# MCU.net
KiCad netlist of a schematic drawn in Altium Designer
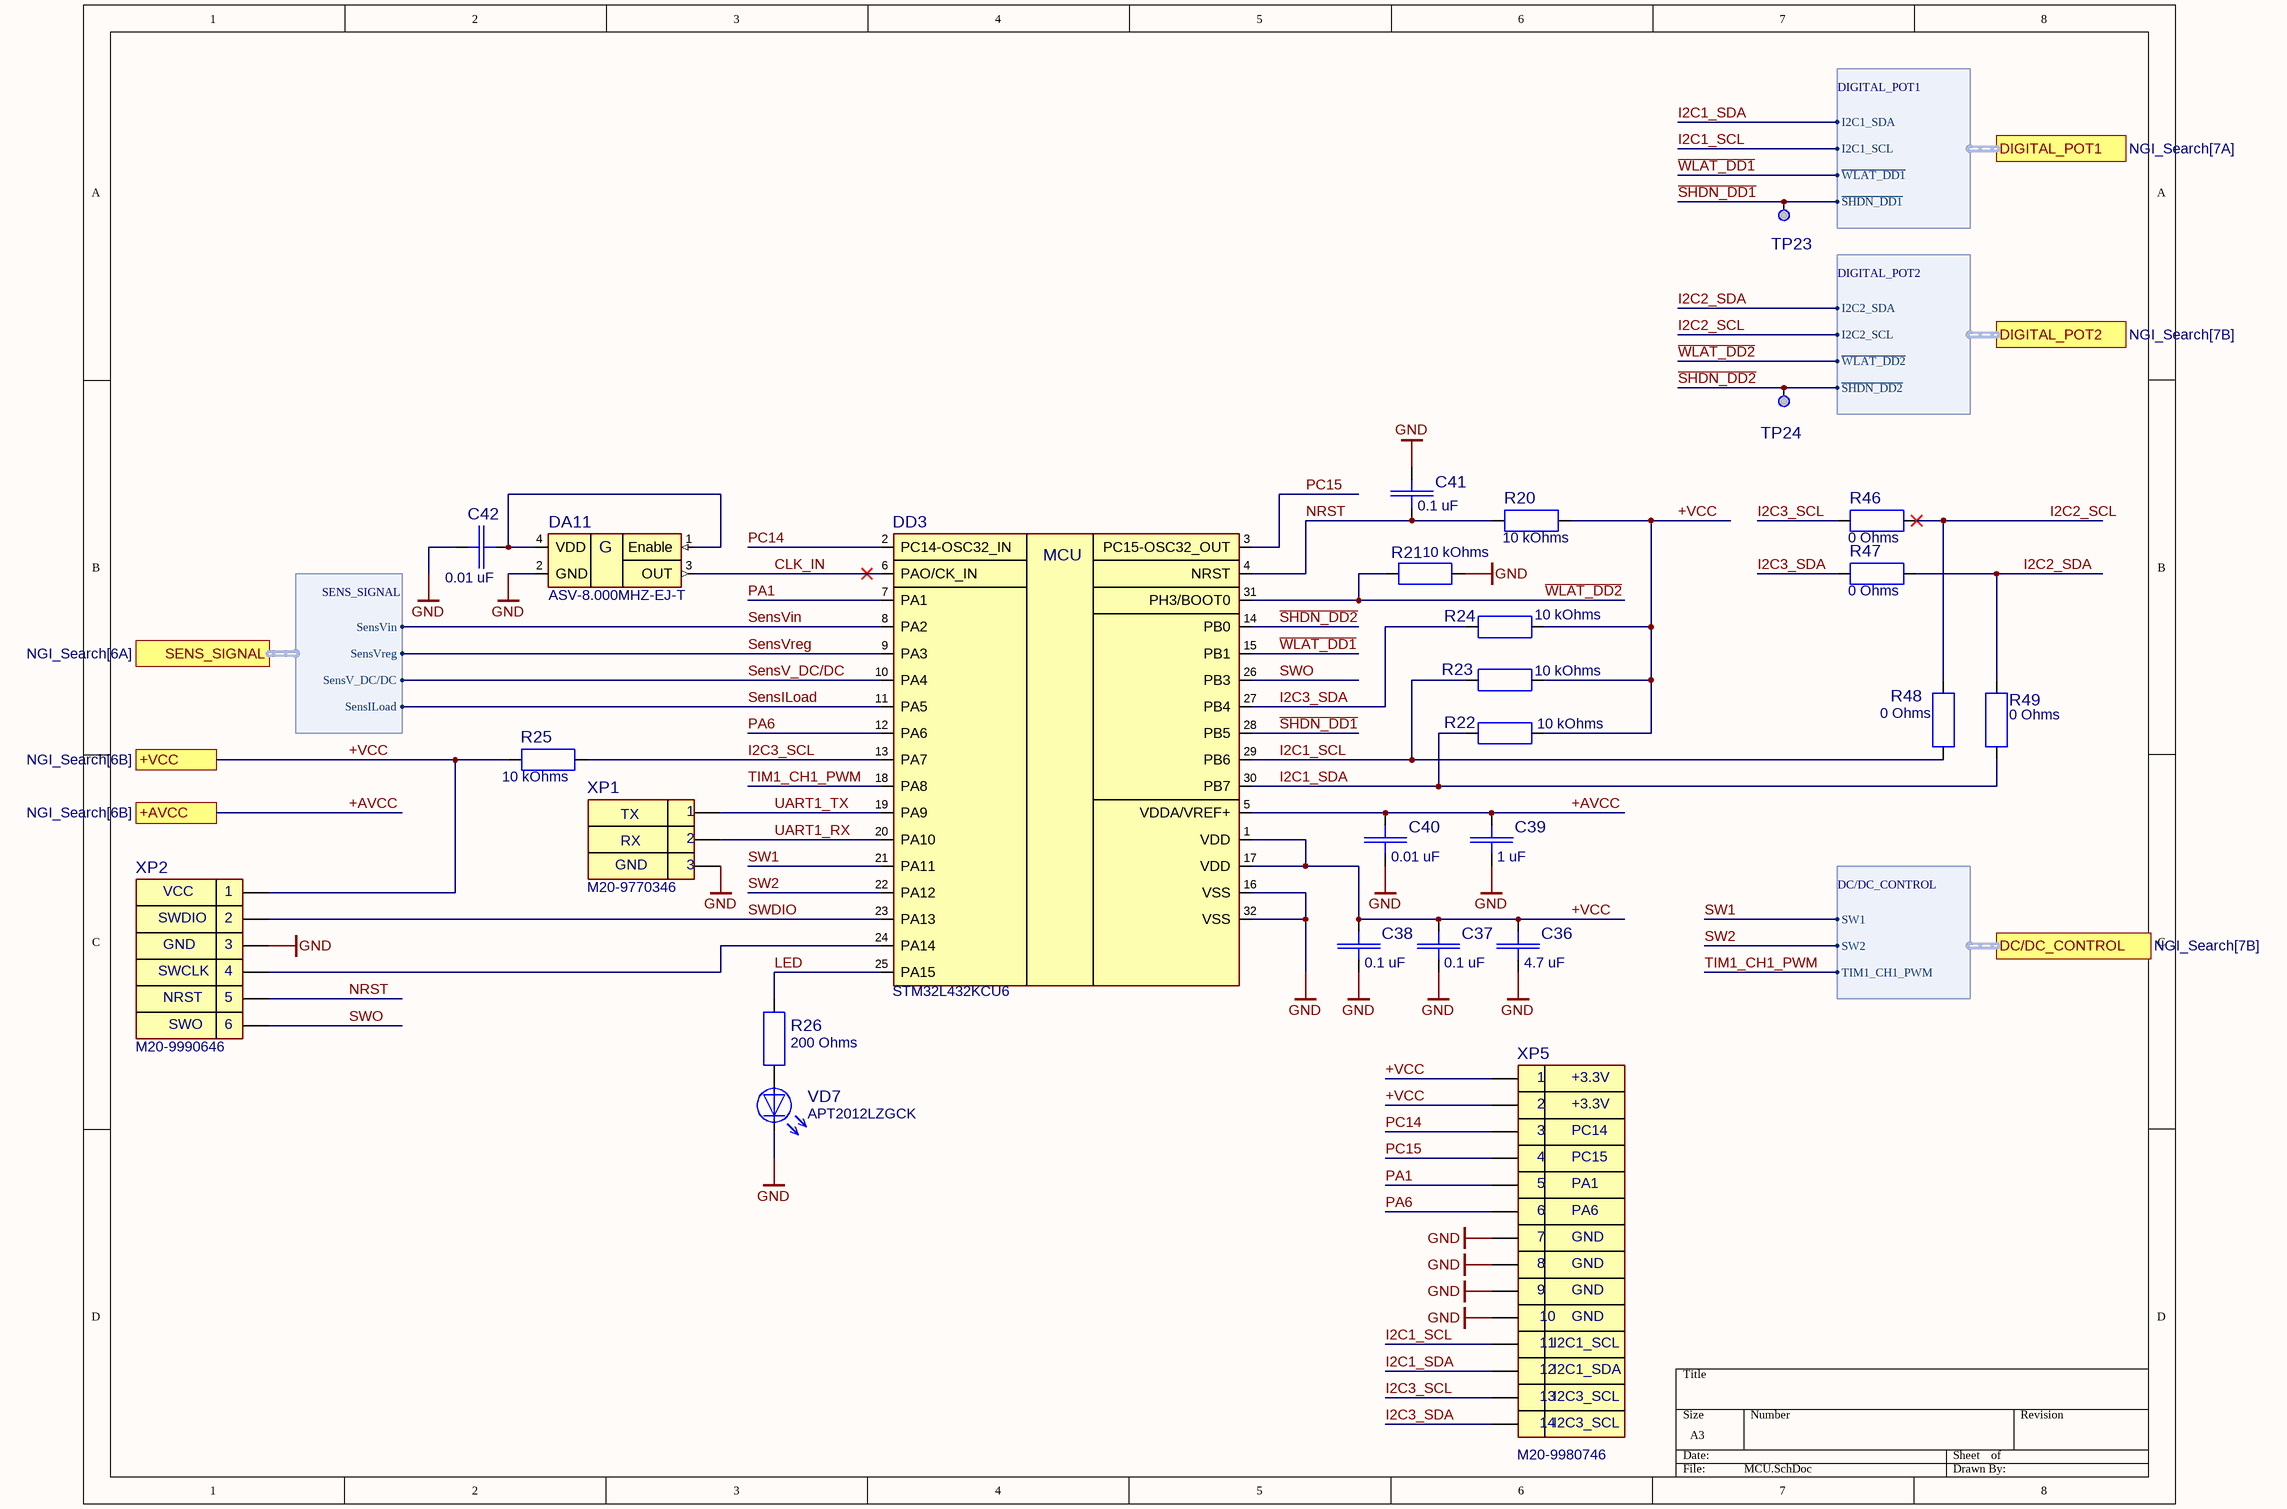
[diagram p0: MCU.SchDoc]

(export (version "E")
  (design (tool "Eeschema 10.0.6"))
  (components
    (comp (ref "C36")
      (value "4.7 uF")
      (footprint "Capacitor0805_THICKNESS1.25")
      (description "Multilayer Ceramic Capacitors MLCC - SMD/SMT 4.7uF+/-10% 25V X5R 0805")
      (fields
        (field (name "MANUFACTURER") "Samsung Electro-Mechanics")
        (field (name "MANUFACTURERPARTNUMBER") "CL21A475KAQNNNF")
      )
      (libsource (lib "NGI_Search") (part "CL21A475KAQNNNF"))
    )
    (comp (ref "C37")
      (value "0.1 uF")
      (footprint "Capacitor0805_THICKNESS0.8")
      (description "Multilayer Ceramic Capacitors MLCC - SMD/SMT 100nF+/-10% 50V X7R 0805")
      (fields (field (name "TOLERANCE") "10%") (field (name "MANUFACTURERPARTNUMBER") "CL21B104KBCNNWC"))
      (libsource (lib "NGI_Search") (part "CL21B104KBCNNWC"))
    )
    (comp (ref "C38")
      (value "0.1 uF")
      (footprint "Capacitor0805_THICKNESS0.8")
      (description "Multilayer Ceramic Capacitors MLCC - SMD/SMT 100nF+/-10% 50V X7R 0805")
      (fields (field (name "TOLERANCE") "10%") (field (name "MANUFACTURERPARTNUMBER") "CL21B104KBCNNWC"))
      (libsource (lib "NGI_Search") (part "CL21B104KBCNNWC"))
    )
    (comp (ref "C39")
      (value "1 uF")
      (footprint "Capacitor0805_THICKNESS1.25")
      (description "Multilayer Ceramic Capacitors MLCC - SMD/SMT 1uF+/-10% 25V X7R 20 0805")
      (fields
        (field (name "MANUFACTURER") "Samsung Electro-Mechanics")
        (field (name "MANUFACTURERPARTNUMBER") "CL21B105KAFNFNE")
      )
      (libsource (lib "NGI_Search") (part "CL21B105KAFNFNE"))
    )
    (comp (ref "C40")
      (value "0.01 uF")
      (footprint "Capacitor0805_THICKNESS0.8")
      (description "Multilayer Ceramic Capacitors MLCC - SMD/SMT 10nF+/-10% 50V X7R 2 0805")
      (fields
        (field (name "MANUFACTURER") "Samsung Electro-Mechanics")
        (field (name "MANUFACTURERPARTNUMBER") "CL21B103KBANNNL")
      )
      (libsource (lib "NGI_Search") (part "CL21B103KBANNNL"))
    )
    (comp (ref "C41")
      (value "0.1 uF")
      (footprint "Capacitor0805_THICKNESS0.8")
      (description "Multilayer Ceramic Capacitors MLCC - SMD/SMT 100nF+/-10% 50V X7R 0805")
      (fields (field (name "TOLERANCE") "10%") (field (name "MANUFACTURERPARTNUMBER") "CL21B104KBCNNWC"))
      (libsource (lib "NGI_Search") (part "CL21B104KBCNNWC"))
    )
    (comp (ref "C42")
      (value "0.01 uF")
      (footprint "Capacitor0805_THICKNESS0.8")
      (description "Multilayer Ceramic Capacitors MLCC - SMD/SMT 10nF+/-10% 50V X7R 2 0805")
      (fields
        (field (name "MANUFACTURER") "Samsung Electro-Mechanics")
        (field (name "MANUFACTURERPARTNUMBER") "CL21B103KBANNNL")
      )
      (libsource (lib "NGI_Search") (part "CL21B103KBANNNL"))
    )
    (comp (ref "DA11")
      (value "ASV-8.000MHZ-EJ-T")
      (footprint "HCMOS 7 mm x 5 mm")
      (description "Standard Clock Oscillators XTAL OSC XO 8.0000MHZ HCMOS SMD")
      (fields (field (name "MANUFACTURER") "ABRACON") (field (name "MOUSER PART NUMBER") "815-ASV-8-EJ-T"))
      (libsource (lib "NGI_Search") (part "ASV-8.000MHZ-EJ-T"))
    )
    (comp (ref "DD3")
      (value "STM32L432KCU6")
      (footprint "UFQFPN-32")
      (description "ARM Microcontrollers - MCU Ultra-low-power FPU Arm Cortex-M4 MCU 80 MHz 256 Kbytes of Flash , USB")
      (fields
        (field (name "MANUFACTURER") "STMicroelectronics")
        (field (name "MOUSER PART NUMBER") "511-STM32L432KCU6")
      )
      (libsource (lib "NGI_Search") (part "STM32L432KCU6"))
    )
    (comp (ref "R20")
      (value "10 kOhms")
      (footprint "Resistor0805_THICKNESS0.6")
      (description "Thick Film Resistors 10 kOhms 125 mW 0805 1%")
      (fields (field (name "MANUFACTURER") "YAGEO") (field (name "MANUFACTURERPARTNUMBER") "RC0805FR-0710KL"))
      (libsource (lib "NGI_Search") (part "RC0805FR-0710KL"))
    )
    (comp (ref "R21")
      (value "10 kOhms")
      (footprint "Resistor0805_THICKNESS0.6")
      (description "Thick Film Resistors 10 kOhms 125 mW 0805 1%")
      (fields (field (name "MANUFACTURER") "YAGEO") (field (name "MANUFACTURERPARTNUMBER") "RC0805FR-0710KL"))
      (libsource (lib "NGI_Search") (part "RC0805FR-0710KL"))
    )
    (comp (ref "R22")
      (value "10 kOhms")
      (footprint "Resistor0805_THICKNESS0.6")
      (description "Thick Film Resistors 10 kOhms 125 mW 0805 1%")
      (fields (field (name "MANUFACTURER") "YAGEO") (field (name "MANUFACTURERPARTNUMBER") "RC0805FR-0710KL"))
      (libsource (lib "NGI_Search") (part "RC0805FR-0710KL"))
    )
    (comp (ref "R23")
      (value "10 kOhms")
      (footprint "Resistor0805_THICKNESS0.6")
      (description "Thick Film Resistors 10 kOhms 125 mW 0805 1%")
      (fields (field (name "MANUFACTURER") "YAGEO") (field (name "MANUFACTURERPARTNUMBER") "RC0805FR-0710KL"))
      (libsource (lib "NGI_Search") (part "RC0805FR-0710KL"))
    )
    (comp (ref "R24")
      (value "10 kOhms")
      (footprint "Resistor0805_THICKNESS0.6")
      (description "Thick Film Resistors 10 kOhms 125 mW 0805 1%")
      (fields (field (name "MANUFACTURER") "YAGEO") (field (name "MANUFACTURERPARTNUMBER") "RC0805FR-0710KL"))
      (libsource (lib "NGI_Search") (part "RC0805FR-0710KL"))
    )
    (comp (ref "R25")
      (value "10 kOhms")
      (footprint "Resistor0805_THICKNESS0.6")
      (description "Thick Film Resistors 10 kOhms 125 mW 0805 1%")
      (fields (field (name "MANUFACTURER") "YAGEO") (field (name "MANUFACTURERPARTNUMBER") "RC0805FR-0710KL"))
      (libsource (lib "NGI_Search") (part "RC0805FR-0710KL"))
    )
    (comp (ref "R26")
      (value "200 Ohms")
      (footprint "Resistor0805_THICKNESS0.6")
      (description "Thick Film Resistors 200Ohms 1/8W 0805 1%")
      (fields
        (field (name "MANUFACTURER") "YAGEO")
        (field (name "MANUFACTURERPARTNUMBER") "RC0805FR-10200RL")
      )
      (libsource (lib "NGI_Search") (part "RC0805FR-10200RL"))
    )
    (comp (ref "R46")
      (value "0 Ohms")
      (footprint "Resistor0805_THICKNESS0.6")
      (description "Thick Film Resistors 0 Ohms 125 mW 0805 1%")
      (fields (field (name "MANUFACTURER") "YAGEO") (field (name "MANUFACTURERPARTNUMBER") "RC0805FR-070RL"))
      (libsource (lib "NGI_Search") (part "RC0805FR-070RL"))
    )
    (comp (ref "R47")
      (value "0 Ohms")
      (footprint "Resistor0805_THICKNESS0.6")
      (description "Thick Film Resistors 0 Ohms 125 mW 0805 1%")
      (fields (field (name "MANUFACTURER") "YAGEO") (field (name "MANUFACTURERPARTNUMBER") "RC0805FR-070RL"))
      (libsource (lib "NGI_Search") (part "RC0805FR-070RL"))
    )
    (comp (ref "R48")
      (value "0 Ohms")
      (footprint "Resistor0805_THICKNESS0.6")
      (description "Thick Film Resistors 0 Ohms 125 mW 0805 1%")
      (fields (field (name "MANUFACTURER") "YAGEO") (field (name "MANUFACTURERPARTNUMBER") "RC0805FR-070RL"))
      (libsource (lib "NGI_Search") (part "RC0805FR-070RL"))
    )
    (comp (ref "R49")
      (value "0 Ohms")
      (footprint "Resistor0805_THICKNESS0.6")
      (description "Thick Film Resistors 0 Ohms 125 mW 0805 1%")
      (fields (field (name "MANUFACTURER") "YAGEO") (field (name "MANUFACTURERPARTNUMBER") "RC0805FR-070RL"))
      (libsource (lib "NGI_Search") (part "RC0805FR-070RL"))
    )
    (comp (ref "TP23")
      (value "test point")
      (footprint "test point")
      (libsource (lib "NGI_Search") (part "test point"))
    )
    (comp (ref "TP24")
      (value "test point")
      (footprint "test point")
      (libsource (lib "NGI_Search") (part "test point"))
    )
    (comp (ref "VD7")
      (value "APT2012LZGCK")
      (footprint "APT2012LZGCK0805_LEDs")
      (description "Standard LEDs - SMD 2.0X1.2MM LOW CRNT")
      (fields
        (field (name "MANUFACTURER") "Kingbright")
        (field (name "MOUSER PART NUMBER") "604-APT2012LZGCK")
      )
      (libsource (lib "NGI_Search") (part "APT2012LZGCK"))
    )
    (comp (ref "XP1")
      (value "M20-9770346")
      (footprint "3 VERTICAL PIN Pitch: 2.54 mm")
      (description "Headers & Wire Housings 03 SIL VERTICAL PIN HEADER TIN")
      (fields (field (name "MANUFACTURER") "Harwin") (field (name "MOUSER PART NUMBER") "855-M20-9770346"))
      (libsource (lib "NGI_Search") (part "M20-9770346"))
    )
    (comp (ref "XP2")
      (value "M20-9990646")
      (footprint "6 VERTICAL PIN Pitch: 2.54 mm")
      (description "Headers & Wire Housings 06 SIL VERTICAL PIN HEADER TIN")
      (fields (field (name "MANUFACTURER") "Harwin"))
      (libsource (lib "NGI_Search") (part "M20-9990646"))
    )
    (comp (ref "XP5")
      (value "M20-9980746")
      (footprint "M20-9980746")
      (description "Headers & Wire Housings 07+07 DIL VERTICAL PIN HEADER TIN")
      (fields (field (name "MANUFACTURER") "Harwin") (field (name "MOUSER PART NUMBER") "855-M20-9980746"))
      (libsource (lib "NGI_Search") (part "M20-9980746"))
    )
  )
  (nets
    (net (code "5") (name "/+AVCC") (class "Default")
      (node (ref "C39") (pin "2") (pinfunction "2_2") (pintype "passive"))
      (node (ref "C40") (pin "2") (pinfunction "2_2") (pintype "passive"))
      (node (ref "DD3") (pin "5") (pinfunction "VDDA/VREF+_5") (pintype "power_in"))
    )
    (net (code "6") (name "/+VCC") (class "Default")
      (node (ref "C36") (pin "2") (pinfunction "2_2") (pintype "passive"))
      (node (ref "C37") (pin "2") (pinfunction "2_2") (pintype "passive"))
      (node (ref "C38") (pin "2") (pinfunction "2_2") (pintype "passive"))
      (node (ref "DD3") (pin "1") (pinfunction "VDD_1") (pintype "power_in"))
      (node (ref "DD3") (pin "17") (pinfunction "VDD_17") (pintype "power_in"))
      (node (ref "R20") (pin "2") (pinfunction "2_2") (pintype "passive"))
      (node (ref "R22") (pin "1") (pinfunction "1_1") (pintype "passive"))
      (node (ref "R23") (pin "2") (pinfunction "2_2") (pintype "passive"))
      (node (ref "R24") (pin "1") (pinfunction "1_1") (pintype "passive"))
      (node (ref "R25") (pin "1") (pinfunction "1_1") (pintype "passive"))
      (node (ref "XP2") (pin "1") (pintype "passive"))
      (node (ref "XP5") (pin "1") (pintype "passive"))
      (node (ref "XP5") (pin "2") (pintype "passive"))
    )
    (net (code "7") (name "/CLK_IN") (class "Default")
      (node (ref "DA11") (pin "3") (pinfunction "OUT_3") (pintype "output"))
      (node (ref "DD3") (pin "6") (pinfunction "PAO/CK_IN_6") (pintype "bidirectional"))
    )
    (net (code "8") (name "/I2C1_SCL") (class "Default")
      (node (ref "DD3") (pin "29") (pinfunction "PB6_29") (pintype "bidirectional"))
      (node (ref "R23") (pin "1") (pinfunction "1_1") (pintype "passive"))
      (node (ref "R48") (pin "1") (pinfunction "1_1") (pintype "passive"))
      (node (ref "XP5") (pin "11") (pinfunction "11_11") (pintype "passive"))
    )
    (net (code "9") (name "/I2C1_SDA") (class "Default")
      (node (ref "DD3") (pin "30") (pinfunction "PB7_30") (pintype "bidirectional"))
      (node (ref "R22") (pin "2") (pinfunction "2_2") (pintype "passive"))
      (node (ref "R49") (pin "1") (pinfunction "1_1") (pintype "passive"))
      (node (ref "XP5") (pin "12") (pinfunction "12_12") (pintype "passive"))
    )
    (net (code "10") (name "/I2C2_SCL") (class "Default")
      (node (ref "R46") (pin "2") (pinfunction "2_2") (pintype "passive"))
      (node (ref "R48") (pin "2") (pinfunction "2_2") (pintype "passive"))
    )
    (net (code "11") (name "/I2C2_SDA") (class "Default")
      (node (ref "R47") (pin "2") (pinfunction "2_2") (pintype "passive"))
      (node (ref "R49") (pin "2") (pinfunction "2_2") (pintype "passive"))
    )
    (net (code "12") (name "/I2C3_SCL") (class "Default")
      (node (ref "DD3") (pin "13") (pinfunction "PA7_13") (pintype "bidirectional"))
      (node (ref "R25") (pin "2") (pinfunction "2_2") (pintype "passive"))
      (node (ref "R46") (pin "1") (pinfunction "1_1") (pintype "passive"))
      (node (ref "XP5") (pin "13") (pinfunction "13_13") (pintype "passive"))
    )
    (net (code "13") (name "/I2C3_SDA") (class "Default")
      (node (ref "DD3") (pin "27") (pinfunction "PB4_27") (pintype "bidirectional"))
      (node (ref "R24") (pin "2") (pinfunction "2_2") (pintype "passive"))
      (node (ref "R47") (pin "1") (pinfunction "1_1") (pintype "passive"))
      (node (ref "XP5") (pin "14") (pinfunction "14_14") (pintype "passive"))
    )
    (net (code "14") (name "/LED") (class "Default")
      (node (ref "DD3") (pin "25") (pinfunction "PA15_25") (pintype "bidirectional"))
      (node (ref "R26") (pin "2") (pinfunction "2_2") (pintype "passive"))
    )
    (net (code "15") (name "/NRST") (class "Default")
      (node (ref "C41") (pin "2") (pinfunction "2_2") (pintype "passive"))
      (node (ref "DD3") (pin "4") (pinfunction "NRST_4") (pintype "bidirectional"))
      (node (ref "R20") (pin "1") (pinfunction "1_1") (pintype "passive"))
      (node (ref "XP2") (pin "5") (pintype "passive"))
    )
    (net (code "16") (name "/PA1") (class "Default")
      (node (ref "DD3") (pin "7") (pinfunction "PA1_7") (pintype "bidirectional"))
      (node (ref "XP5") (pin "5") (pintype "passive"))
    )
    (net (code "17") (name "/PA6") (class "Default")
      (node (ref "DD3") (pin "12") (pinfunction "PA6_12") (pintype "bidirectional"))
      (node (ref "XP5") (pin "6") (pintype "passive"))
    )
    (net (code "18") (name "/PC14") (class "Default")
      (node (ref "DD3") (pin "2") (pinfunction "PC14-OSC32_IN_2") (pintype "bidirectional"))
      (node (ref "XP5") (pin "3") (pintype "passive"))
    )
    (net (code "19") (name "/PC15") (class "Default")
      (node (ref "DD3") (pin "3") (pinfunction "PC15-OSC32_OUT_3") (pintype "bidirectional"))
      (node (ref "XP5") (pin "4") (pintype "passive"))
    )
    (net (code "20") (name "/SW1") (class "Default")
      (node (ref "DD3") (pin "21") (pinfunction "PA11_21") (pintype "bidirectional"))
    )
    (net (code "21") (name "/SW2") (class "Default")
      (node (ref "DD3") (pin "22") (pinfunction "PA12_22") (pintype "bidirectional"))
    )
    (net (code "22") (name "/SWDIO") (class "Default")
      (node (ref "DD3") (pin "23") (pinfunction "PA13_23") (pintype "bidirectional"))
      (node (ref "XP2") (pin "2") (pintype "passive"))
    )
    (net (code "23") (name "/SWO") (class "Default")
      (node (ref "DD3") (pin "26") (pinfunction "PB3_26") (pintype "bidirectional"))
      (node (ref "XP2") (pin "6") (pintype "passive"))
    )
    (net (code "24") (name "/SensILoad") (class "Default")
      (node (ref "DD3") (pin "11") (pinfunction "PA5_11") (pintype "bidirectional"))
    )
    (net (code "25") (name "/SensV_DC{slash}DC") (class "Default")
      (node (ref "DD3") (pin "10") (pinfunction "PA4_10") (pintype "bidirectional"))
    )
    (net (code "26") (name "/SensVin") (class "Default")
      (node (ref "DD3") (pin "8") (pinfunction "PA2_8") (pintype "bidirectional"))
    )
    (net (code "27") (name "/SensVreg") (class "Default")
      (node (ref "DD3") (pin "9") (pinfunction "PA3_9") (pintype "bidirectional"))
    )
    (net (code "28") (name "/TIM1_CH1_PWM") (class "Default")
      (node (ref "DD3") (pin "18") (pinfunction "PA8_18") (pintype "bidirectional"))
    )
    (net (code "29") (name "/UART1_RX") (class "Default")
      (node (ref "DD3") (pin "20") (pinfunction "PA10_20") (pintype "bidirectional"))
      (node (ref "XP1") (pin "2") (pintype "passive"))
    )
    (net (code "30") (name "/UART1_TX") (class "Default")
      (node (ref "DD3") (pin "19") (pinfunction "PA9_19") (pintype "bidirectional"))
      (node (ref "XP1") (pin "1") (pintype "passive"))
    )
    (net (code "35") (name "/~{SHDN_DD1}") (class "Default")
      (node (ref "DD3") (pin "28") (pinfunction "PB5_28") (pintype "bidirectional"))
      (node (ref "TP23") (pin "1") (pinfunction "1_1") (pintype "passive"))
    )
    (net (code "36") (name "/~{SHDN_DD2}") (class "Default")
      (node (ref "DD3") (pin "14") (pinfunction "PB0_14") (pintype "bidirectional"))
      (node (ref "TP24") (pin "1") (pinfunction "1_1") (pintype "passive"))
    )
    (net (code "37") (name "/~{WLAT_DD1}") (class "Default")
      (node (ref "DD3") (pin "15") (pinfunction "PB1_15") (pintype "bidirectional"))
    )
    (net (code "38") (name "/~{WLAT_DD2}") (class "Default")
      (node (ref "DD3") (pin "31") (pinfunction "PH3/BOOT0_31") (pintype "bidirectional"))
      (node (ref "R21") (pin "1") (pinfunction "1_1") (pintype "passive"))
    )
    (net (code "39") (name "GND") (class "Default")
      (node (ref "C36") (pin "1") (pinfunction "1_1") (pintype "passive"))
      (node (ref "C37") (pin "1") (pinfunction "1_1") (pintype "passive"))
      (node (ref "C38") (pin "1") (pinfunction "1_1") (pintype "passive"))
      (node (ref "C39") (pin "1") (pinfunction "1_1") (pintype "passive"))
      (node (ref "C40") (pin "1") (pinfunction "1_1") (pintype "passive"))
      (node (ref "C41") (pin "1") (pinfunction "1_1") (pintype "passive"))
      (node (ref "C42") (pin "1") (pinfunction "1_1") (pintype "passive"))
      (node (ref "DA11") (pin "2") (pinfunction "GND_2") (pintype "power_in"))
      (node (ref "DD3") (pin "16") (pinfunction "VSS_16") (pintype "power_in"))
      (node (ref "DD3") (pin "32") (pinfunction "VSS_32") (pintype "power_in"))
      (node (ref "R21") (pin "2") (pinfunction "2_2") (pintype "passive"))
      (node (ref "VD7") (pin "C") (pinfunction "C_C") (pintype "passive"))
      (node (ref "XP1") (pin "3") (pintype "passive"))
      (node (ref "XP2") (pin "3") (pintype "passive"))
      (node (ref "XP5") (pin "10") (pinfunction "10_10") (pintype "passive"))
      (node (ref "XP5") (pin "7") (pinfunction "7_7") (pintype "passive"))
      (node (ref "XP5") (pin "8") (pinfunction "8_8") (pintype "passive"))
      (node (ref "XP5") (pin "9") (pinfunction "9_9") (pintype "passive"))
    )
    (net (code "40") (name "Net-(DA11-Enable)") (class "Default")
      (node (ref "C42") (pin "2") (pinfunction "2_2") (pintype "passive"))
      (node (ref "DA11") (pin "1") (pinfunction "Enable_1") (pintype "input"))
      (node (ref "DA11") (pin "4") (pinfunction "VDD_4") (pintype "power_in"))
    )
    (net (code "41") (name "Net-(DD3-PA14)") (class "Default")
      (node (ref "DD3") (pin "24") (pinfunction "PA14_24") (pintype "bidirectional"))
      (node (ref "XP2") (pin "4") (pintype "passive"))
    )
    (net (code "42") (name "Net-(R26-Pad1)") (class "Default")
      (node (ref "R26") (pin "1") (pinfunction "1_1") (pintype "passive"))
      (node (ref "VD7") (pin "A") (pinfunction "A_A") (pintype "passive"))
    )
  )
)
